# FPGA_Power.net
KiCad netlist of a schematic drawn in Altium Designer
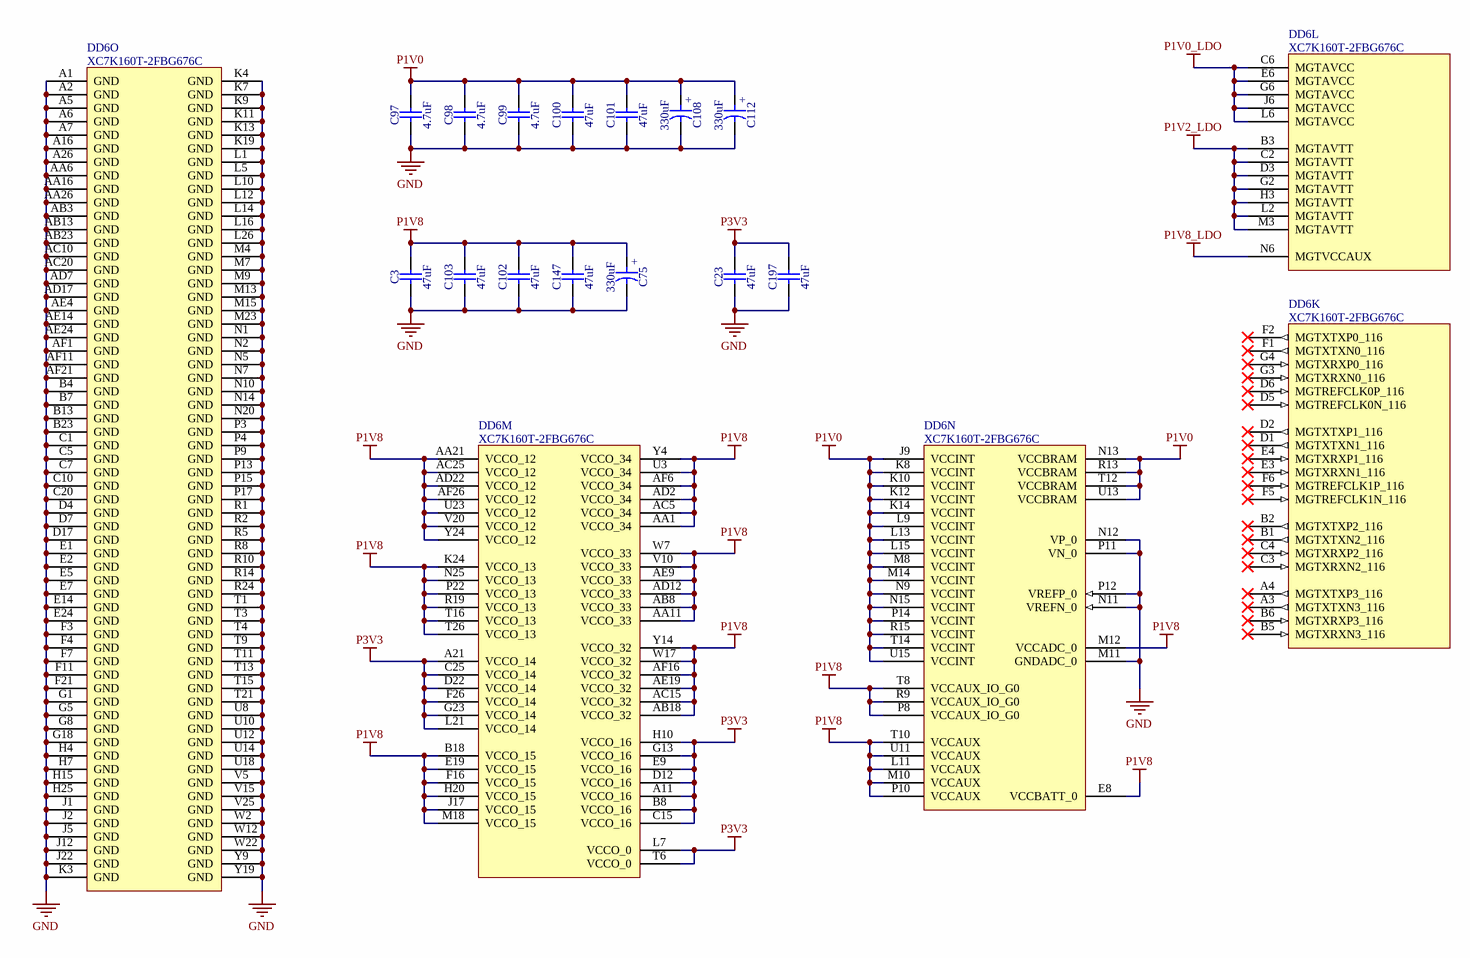
[diagram p0: FPGA_Power.SchDoc]

(export (version "E")
  (design (tool "Eeschema 10.0.6"))
  (components
    (comp (ref "C3")
      (value "47uF")
      (footprint "CAPC3225X270N")
      (description "Non-polarised capacitor")
      (fields
        (field (name "PART NUMBER") "CC1210_47UF_16V_20%_X5R")
        (field (name "VOLTAGE") "16V")
        (field (name "AUTHOR") "CERN DEM MR")
      )
      (libsource (lib "Capacitors") (part "Capacitor - non polarized"))
    )
    (comp (ref "C23")
      (value "47uF")
      (footprint "CAPC3225X270N")
      (description "Non-polarised capacitor")
      (fields
        (field (name "PART NUMBER") "CC1210_47UF_16V_20%_X5R")
        (field (name "VOLTAGE") "16V")
        (field (name "AUTHOR") "CERN DEM MR")
      )
      (libsource (lib "Capacitors") (part "Capacitor - non polarized"))
    )
    (comp (ref "C75")
      (value "330uF")
      (footprint "CAPMP7343X300N")
      (description "Polarised capacitor")
      (fields
        (field (name "PART NUMBER") "CTE7343-30_330UF_4V_20%_PANASONIC_TPF")
        (field (name "VOLTAGE") "4V")
        (field (name "AUTHOR") "CERN DEM HF")
      )
      (libsource (lib "Capacitors") (part "Capacitor - polarized"))
    )
    (comp (ref "C97")
      (value "4.7uF")
      (footprint "CAPC2012X145N")
      (description "Non-polarised capacitor")
      (fields
        (field (name "PART NUMBER") "CC0805_4.7UF_50V_10%_X7R")
        (field (name "VOLTAGE") "50V")
        (field (name "AUTHOR") "CERN DEM JMW")
      )
      (libsource (lib "Capacitors") (part "Capacitor - non polarized"))
    )
    (comp (ref "C98")
      (value "4.7uF")
      (footprint "CAPC2012X145N")
      (description "Non-polarised capacitor")
      (fields
        (field (name "PART NUMBER") "CC0805_4.7UF_50V_10%_X7R")
        (field (name "VOLTAGE") "50V")
        (field (name "AUTHOR") "CERN DEM JMW")
      )
      (libsource (lib "Capacitors") (part "Capacitor - non polarized"))
    )
    (comp (ref "C99")
      (value "4.7uF")
      (footprint "CAPC2012X145N")
      (description "Non-polarised capacitor")
      (fields
        (field (name "PART NUMBER") "CC0805_4.7UF_50V_10%_X7R")
        (field (name "VOLTAGE") "50V")
        (field (name "AUTHOR") "CERN DEM JMW")
      )
      (libsource (lib "Capacitors") (part "Capacitor - non polarized"))
    )
    (comp (ref "C100")
      (value "47uF")
      (footprint "CAPC3225X270N")
      (description "Non-polarised capacitor")
      (fields
        (field (name "PART NUMBER") "CC1210_47UF_16V_20%_X5R")
        (field (name "VOLTAGE") "16V")
        (field (name "AUTHOR") "CERN DEM MR")
      )
      (libsource (lib "Capacitors") (part "Capacitor - non polarized"))
    )
    (comp (ref "C101")
      (value "47uF")
      (footprint "CAPC3225X270N")
      (description "Non-polarised capacitor")
      (fields
        (field (name "PART NUMBER") "CC1210_47UF_16V_20%_X5R")
        (field (name "VOLTAGE") "16V")
        (field (name "AUTHOR") "CERN DEM MR")
      )
      (libsource (lib "Capacitors") (part "Capacitor - non polarized"))
    )
    (comp (ref "C102")
      (value "47uF")
      (footprint "CAPC3225X270N")
      (description "Non-polarised capacitor")
      (fields
        (field (name "PART NUMBER") "CC1210_47UF_16V_20%_X5R")
        (field (name "VOLTAGE") "16V")
        (field (name "AUTHOR") "CERN DEM MR")
      )
      (libsource (lib "Capacitors") (part "Capacitor - non polarized"))
    )
    (comp (ref "C103")
      (value "47uF")
      (footprint "CAPC3225X270N")
      (description "Non-polarised capacitor")
      (fields
        (field (name "PART NUMBER") "CC1210_47UF_16V_20%_X5R")
        (field (name "VOLTAGE") "16V")
        (field (name "AUTHOR") "CERN DEM MR")
      )
      (libsource (lib "Capacitors") (part "Capacitor - non polarized"))
    )
    (comp (ref "C108")
      (value "330uF")
      (footprint "CAPMP7343X190N")
      (description "Polarised capacitor")
      (fields
        (field (name "PART NUMBER") "CTE7343-19_330UF_2.5V_20%_LESR0009_KEMET_T520")
        (field (name "VOLTAGE") "2.5V")
        (field (name "AUTHOR") "CERN DEM HF")
      )
      (libsource (lib "Capacitors") (part "Capacitor - polarized"))
    )
    (comp (ref "C112")
      (value "330uF")
      (footprint "CAPMP7343X190N")
      (description "Polarised capacitor")
      (fields
        (field (name "PART NUMBER") "CTE7343-19_330UF_2.5V_20%_LESR0009_KEMET_T520")
        (field (name "VOLTAGE") "2.5V")
        (field (name "AUTHOR") "CERN DEM HF")
      )
      (libsource (lib "Capacitors") (part "Capacitor - polarized"))
    )
    (comp (ref "C147")
      (value "47uF")
      (footprint "CAPC3225X270N")
      (description "Non-polarised capacitor")
      (fields
        (field (name "PART NUMBER") "CC1210_47UF_16V_20%_X5R")
        (field (name "VOLTAGE") "16V")
        (field (name "AUTHOR") "CERN DEM MR")
      )
      (libsource (lib "Capacitors") (part "Capacitor - non polarized"))
    )
    (comp (ref "C197")
      (value "47uF")
      (footprint "CAPC3225X270N")
      (description "Non-polarised capacitor")
      (fields
        (field (name "PART NUMBER") "CC1210_47UF_16V_20%_X5R")
        (field (name "VOLTAGE") "16V")
        (field (name "AUTHOR") "CERN DEM MR")
      )
      (libsource (lib "Capacitors") (part "Capacitor - non polarized"))
    )
    (comp (ref "DD6")
      (value "XC7K160T-2FBG676C")
      (footprint "BGA676C100P26X26_2700X2700X254")
      (description "KINTEX-7, FPGA, 676-Ball BGA, Pb-Free")
      (fields (field (name "MANUFACTURER") "XILINX") (field (name "AUTHOR") "CERN DEM BC"))
      (libsource (lib "ICs And Semiconductors") (part "XC7K160T-xFBG676"))
    )
  )
  (nets
    (net (code "1") (name "GND") (class "Default")
      (node (ref "C100") (pin "1") (pinfunction "1_1") (pintype "passive"))
      (node (ref "C101") (pin "1") (pinfunction "1_1") (pintype "passive"))
      (node (ref "C102") (pin "1") (pinfunction "1_1") (pintype "passive"))
      (node (ref "C103") (pin "1") (pinfunction "1_1") (pintype "passive"))
      (node (ref "C108") (pin "2") (pinfunction "2_2") (pintype "passive"))
      (node (ref "C112") (pin "2") (pinfunction "2_2") (pintype "passive"))
      (node (ref "C147") (pin "1") (pinfunction "1_1") (pintype "passive"))
      (node (ref "C197") (pin "1") (pinfunction "1_1") (pintype "passive"))
      (node (ref "C23") (pin "1") (pinfunction "1_1") (pintype "passive"))
      (node (ref "C3") (pin "1") (pinfunction "1_1") (pintype "passive"))
      (node (ref "C75") (pin "2") (pinfunction "2_2") (pintype "passive"))
      (node (ref "C97") (pin "1") (pinfunction "1_1") (pintype "passive"))
      (node (ref "C98") (pin "1") (pinfunction "1_1") (pintype "passive"))
      (node (ref "C99") (pin "1") (pinfunction "1_1") (pintype "passive"))
      (node (ref "DD6") (pin "A1") (pinfunction "GND_A1") (pintype "power_in"))
      (node (ref "DD6") (pin "A16") (pinfunction "GND_A16") (pintype "power_in"))
      (node (ref "DD6") (pin "A2") (pinfunction "GND_A2") (pintype "power_in"))
      (node (ref "DD6") (pin "A26") (pinfunction "GND_A26") (pintype "power_in"))
      (node (ref "DD6") (pin "A5") (pinfunction "GND_A5") (pintype "power_in"))
      (node (ref "DD6") (pin "A6") (pinfunction "GND_A6") (pintype "power_in"))
      (node (ref "DD6") (pin "A7") (pinfunction "GND_A7") (pintype "power_in"))
      (node (ref "DD6") (pin "AA16") (pinfunction "GND_AA16") (pintype "power_in"))
      (node (ref "DD6") (pin "AA26") (pinfunction "GND_AA26") (pintype "power_in"))
      (node (ref "DD6") (pin "AA6") (pinfunction "GND_AA6") (pintype "power_in"))
      (node (ref "DD6") (pin "AB13") (pinfunction "GND_AB13") (pintype "power_in"))
      (node (ref "DD6") (pin "AB23") (pinfunction "GND_AB23") (pintype "power_in"))
      (node (ref "DD6") (pin "AB3") (pinfunction "GND_AB3") (pintype "power_in"))
      (node (ref "DD6") (pin "AC10") (pinfunction "GND_AC10") (pintype "power_in"))
      (node (ref "DD6") (pin "AC20") (pinfunction "GND_AC20") (pintype "power_in"))
      (node (ref "DD6") (pin "AD17") (pinfunction "GND_AD17") (pintype "power_in"))
      (node (ref "DD6") (pin "AD7") (pinfunction "GND_AD7") (pintype "power_in"))
      (node (ref "DD6") (pin "AE14") (pinfunction "GND_AE14") (pintype "power_in"))
      (node (ref "DD6") (pin "AE24") (pinfunction "GND_AE24") (pintype "power_in"))
      (node (ref "DD6") (pin "AE4") (pinfunction "GND_AE4") (pintype "power_in"))
      (node (ref "DD6") (pin "AF1") (pinfunction "GND_AF1") (pintype "power_in"))
      (node (ref "DD6") (pin "AF11") (pinfunction "GND_AF11") (pintype "power_in"))
      (node (ref "DD6") (pin "AF21") (pinfunction "GND_AF21") (pintype "power_in"))
      (node (ref "DD6") (pin "B13") (pinfunction "GND_B13") (pintype "power_in"))
      (node (ref "DD6") (pin "B23") (pinfunction "GND_B23") (pintype "power_in"))
      (node (ref "DD6") (pin "B4") (pinfunction "GND_B4") (pintype "power_in"))
      (node (ref "DD6") (pin "B7") (pinfunction "GND_B7") (pintype "power_in"))
      (node (ref "DD6") (pin "C1") (pinfunction "GND_C1") (pintype "power_in"))
      (node (ref "DD6") (pin "C10") (pinfunction "GND_C10") (pintype "power_in"))
      (node (ref "DD6") (pin "C20") (pinfunction "GND_C20") (pintype "power_in"))
      (node (ref "DD6") (pin "C5") (pinfunction "GND_C5") (pintype "power_in"))
      (node (ref "DD6") (pin "C7") (pinfunction "GND_C7") (pintype "power_in"))
      (node (ref "DD6") (pin "D17") (pinfunction "GND_D17") (pintype "power_in"))
      (node (ref "DD6") (pin "D4") (pinfunction "GND_D4") (pintype "power_in"))
      (node (ref "DD6") (pin "D7") (pinfunction "GND_D7") (pintype "power_in"))
      (node (ref "DD6") (pin "E1") (pinfunction "GND_E1") (pintype "power_in"))
      (node (ref "DD6") (pin "E14") (pinfunction "GND_E14") (pintype "power_in"))
      (node (ref "DD6") (pin "E2") (pinfunction "GND_E2") (pintype "power_in"))
      (node (ref "DD6") (pin "E24") (pinfunction "GND_E24") (pintype "power_in"))
      (node (ref "DD6") (pin "E5") (pinfunction "GND_E5") (pintype "power_in"))
      (node (ref "DD6") (pin "E7") (pinfunction "GND_E7") (pintype "power_in"))
      (node (ref "DD6") (pin "F11") (pinfunction "GND_F11") (pintype "power_in"))
      (node (ref "DD6") (pin "F21") (pinfunction "GND_F21") (pintype "power_in"))
      (node (ref "DD6") (pin "F3") (pinfunction "GND_F3") (pintype "power_in"))
      (node (ref "DD6") (pin "F4") (pinfunction "GND_F4") (pintype "power_in"))
      (node (ref "DD6") (pin "F7") (pinfunction "GND_F7") (pintype "power_in"))
      (node (ref "DD6") (pin "G1") (pinfunction "GND_G1") (pintype "power_in"))
      (node (ref "DD6") (pin "G18") (pinfunction "GND_G18") (pintype "power_in"))
      (node (ref "DD6") (pin "G5") (pinfunction "GND_G5") (pintype "power_in"))
      (node (ref "DD6") (pin "G8") (pinfunction "GND_G8") (pintype "power_in"))
      (node (ref "DD6") (pin "H15") (pinfunction "GND_H15") (pintype "power_in"))
      (node (ref "DD6") (pin "H25") (pinfunction "GND_H25") (pintype "power_in"))
      (node (ref "DD6") (pin "H4") (pinfunction "GND_H4") (pintype "power_in"))
      (node (ref "DD6") (pin "H7") (pinfunction "GND_H7") (pintype "power_in"))
      (node (ref "DD6") (pin "J1") (pinfunction "GND_J1") (pintype "power_in"))
      (node (ref "DD6") (pin "J12") (pinfunction "GND_J12") (pintype "power_in"))
      (node (ref "DD6") (pin "J2") (pinfunction "GND_J2") (pintype "power_in"))
      (node (ref "DD6") (pin "J22") (pinfunction "GND_J22") (pintype "power_in"))
      (node (ref "DD6") (pin "J5") (pinfunction "GND_J5") (pintype "power_in"))
      (node (ref "DD6") (pin "K11") (pinfunction "GND_K11") (pintype "power_in"))
      (node (ref "DD6") (pin "K13") (pinfunction "GND_K13") (pintype "power_in"))
      (node (ref "DD6") (pin "K19") (pinfunction "GND_K19") (pintype "power_in"))
      (node (ref "DD6") (pin "K3") (pinfunction "GND_K3") (pintype "power_in"))
      (node (ref "DD6") (pin "K4") (pinfunction "GND_K4") (pintype "power_in"))
      (node (ref "DD6") (pin "K7") (pinfunction "GND_K7") (pintype "power_in"))
      (node (ref "DD6") (pin "K9") (pinfunction "GND_K9") (pintype "power_in"))
      (node (ref "DD6") (pin "L1") (pinfunction "GND_L1") (pintype "power_in"))
      (node (ref "DD6") (pin "L10") (pinfunction "GND_L10") (pintype "power_in"))
      (node (ref "DD6") (pin "L12") (pinfunction "GND_L12") (pintype "power_in"))
      (node (ref "DD6") (pin "L14") (pinfunction "GND_L14") (pintype "power_in"))
      (node (ref "DD6") (pin "L16") (pinfunction "GND_L16") (pintype "power_in"))
      (node (ref "DD6") (pin "L26") (pinfunction "GND_L26") (pintype "power_in"))
      (node (ref "DD6") (pin "L5") (pinfunction "GND_L5") (pintype "power_in"))
      (node (ref "DD6") (pin "M11") (pinfunction "GNDADC_0_M11") (pintype "power_in"))
      (node (ref "DD6") (pin "M13") (pinfunction "GND_M13") (pintype "power_in"))
      (node (ref "DD6") (pin "M15") (pinfunction "GND_M15") (pintype "power_in"))
      (node (ref "DD6") (pin "M23") (pinfunction "GND_M23") (pintype "power_in"))
      (node (ref "DD6") (pin "M4") (pinfunction "GND_M4") (pintype "power_in"))
      (node (ref "DD6") (pin "M7") (pinfunction "GND_M7") (pintype "power_in"))
      (node (ref "DD6") (pin "M9") (pinfunction "GND_M9") (pintype "power_in"))
      (node (ref "DD6") (pin "N1") (pinfunction "GND_N1") (pintype "power_in"))
      (node (ref "DD6") (pin "N10") (pinfunction "GND_N10") (pintype "power_in"))
      (node (ref "DD6") (pin "N11") (pinfunction "VREFN_0_N11") (pintype "input"))
      (node (ref "DD6") (pin "N12") (pinfunction "VP_0_N12") (pintype "power_in"))
      (node (ref "DD6") (pin "N14") (pinfunction "GND_N14") (pintype "power_in"))
      (node (ref "DD6") (pin "N2") (pinfunction "GND_N2") (pintype "power_in"))
      (node (ref "DD6") (pin "N20") (pinfunction "GND_N20") (pintype "power_in"))
      (node (ref "DD6") (pin "N5") (pinfunction "GND_N5") (pintype "power_in"))
      (node (ref "DD6") (pin "N7") (pinfunction "GND_N7") (pintype "power_in"))
      (node (ref "DD6") (pin "P11") (pinfunction "VN_0_P11") (pintype "power_in"))
      (node (ref "DD6") (pin "P12") (pinfunction "VREFP_0_P12") (pintype "input"))
      (node (ref "DD6") (pin "P13") (pinfunction "GND_P13") (pintype "power_in"))
      (node (ref "DD6") (pin "P15") (pinfunction "GND_P15") (pintype "power_in"))
      (node (ref "DD6") (pin "P17") (pinfunction "GND_P17") (pintype "power_in"))
      (node (ref "DD6") (pin "P3") (pinfunction "GND_P3") (pintype "power_in"))
      (node (ref "DD6") (pin "P4") (pinfunction "GND_P4") (pintype "power_in"))
      (node (ref "DD6") (pin "P9") (pinfunction "GND_P9") (pintype "power_in"))
      (node (ref "DD6") (pin "R1") (pinfunction "GND_R1") (pintype "power_in"))
      (node (ref "DD6") (pin "R10") (pinfunction "GND_R10") (pintype "power_in"))
      (node (ref "DD6") (pin "R14") (pinfunction "GND_R14") (pintype "power_in"))
      (node (ref "DD6") (pin "R2") (pinfunction "GND_R2") (pintype "power_in"))
      (node (ref "DD6") (pin "R24") (pinfunction "GND_R24") (pintype "power_in"))
      (node (ref "DD6") (pin "R5") (pinfunction "GND_R5") (pintype "power_in"))
      (node (ref "DD6") (pin "R8") (pinfunction "GND_R8") (pintype "power_in"))
      (node (ref "DD6") (pin "T1") (pinfunction "GND_T1") (pintype "power_in"))
      (node (ref "DD6") (pin "T11") (pinfunction "GND_T11") (pintype "power_in"))
      (node (ref "DD6") (pin "T13") (pinfunction "GND_T13") (pintype "power_in"))
      (node (ref "DD6") (pin "T15") (pinfunction "GND_T15") (pintype "power_in"))
      (node (ref "DD6") (pin "T21") (pinfunction "GND_T21") (pintype "power_in"))
      (node (ref "DD6") (pin "T3") (pinfunction "GND_T3") (pintype "power_in"))
      (node (ref "DD6") (pin "T4") (pinfunction "GND_T4") (pintype "power_in"))
      (node (ref "DD6") (pin "T9") (pinfunction "GND_T9") (pintype "power_in"))
      (node (ref "DD6") (pin "U10") (pinfunction "GND_U10") (pintype "power_in"))
      (node (ref "DD6") (pin "U12") (pinfunction "GND_U12") (pintype "power_in"))
      (node (ref "DD6") (pin "U14") (pinfunction "GND_U14") (pintype "power_in"))
      (node (ref "DD6") (pin "U18") (pinfunction "GND_U18") (pintype "power_in"))
      (node (ref "DD6") (pin "U8") (pinfunction "GND_U8") (pintype "power_in"))
      (node (ref "DD6") (pin "V15") (pinfunction "GND_V15") (pintype "power_in"))
      (node (ref "DD6") (pin "V25") (pinfunction "GND_V25") (pintype "power_in"))
      (node (ref "DD6") (pin "V5") (pinfunction "GND_V5") (pintype "power_in"))
      (node (ref "DD6") (pin "W12") (pinfunction "GND_W12") (pintype "power_in"))
      (node (ref "DD6") (pin "W2") (pinfunction "GND_W2") (pintype "power_in"))
      (node (ref "DD6") (pin "W22") (pinfunction "GND_W22") (pintype "power_in"))
      (node (ref "DD6") (pin "Y19") (pinfunction "GND_Y19") (pintype "power_in"))
      (node (ref "DD6") (pin "Y9") (pinfunction "GND_Y9") (pintype "power_in"))
    )
    (net (code "2") (name "P1V0") (class "Default")
      (node (ref "C100") (pin "2") (pinfunction "2_2") (pintype "passive"))
      (node (ref "C101") (pin "2") (pinfunction "2_2") (pintype "passive"))
      (node (ref "C108") (pin "1") (pinfunction "1_1") (pintype "passive"))
      (node (ref "C112") (pin "1") (pinfunction "1_1") (pintype "passive"))
      (node (ref "C97") (pin "2") (pinfunction "2_2") (pintype "passive"))
      (node (ref "C98") (pin "2") (pinfunction "2_2") (pintype "passive"))
      (node (ref "C99") (pin "2") (pinfunction "2_2") (pintype "passive"))
      (node (ref "DD6") (pin "J9") (pinfunction "VCCINT_J9") (pintype "power_in"))
      (node (ref "DD6") (pin "K10") (pinfunction "VCCINT_K10") (pintype "power_in"))
      (node (ref "DD6") (pin "K12") (pinfunction "VCCINT_K12") (pintype "power_in"))
      (node (ref "DD6") (pin "K14") (pinfunction "VCCINT_K14") (pintype "power_in"))
      (node (ref "DD6") (pin "K8") (pinfunction "VCCINT_K8") (pintype "power_in"))
      (node (ref "DD6") (pin "L13") (pinfunction "VCCINT_L13") (pintype "power_in"))
      (node (ref "DD6") (pin "L15") (pinfunction "VCCINT_L15") (pintype "power_in"))
      (node (ref "DD6") (pin "L9") (pinfunction "VCCINT_L9") (pintype "power_in"))
      (node (ref "DD6") (pin "M14") (pinfunction "VCCINT_M14") (pintype "power_in"))
      (node (ref "DD6") (pin "M8") (pinfunction "VCCINT_M8") (pintype "power_in"))
      (node (ref "DD6") (pin "N13") (pinfunction "VCCBRAM_N13") (pintype "power_in"))
      (node (ref "DD6") (pin "N15") (pinfunction "VCCINT_N15") (pintype "power_in"))
      (node (ref "DD6") (pin "N9") (pinfunction "VCCINT_N9") (pintype "power_in"))
      (node (ref "DD6") (pin "P14") (pinfunction "VCCINT_P14") (pintype "power_in"))
      (node (ref "DD6") (pin "R13") (pinfunction "VCCBRAM_R13") (pintype "power_in"))
      (node (ref "DD6") (pin "R15") (pinfunction "VCCINT_R15") (pintype "power_in"))
      (node (ref "DD6") (pin "T12") (pinfunction "VCCBRAM_T12") (pintype "power_in"))
      (node (ref "DD6") (pin "T14") (pinfunction "VCCINT_T14") (pintype "power_in"))
      (node (ref "DD6") (pin "U13") (pinfunction "VCCBRAM_U13") (pintype "power_in"))
      (node (ref "DD6") (pin "U15") (pinfunction "VCCINT_U15") (pintype "power_in"))
    )
    (net (code "3") (name "P1V0_LDO") (class "Default")
      (node (ref "DD6") (pin "C6") (pinfunction "MGTAVCC_C6") (pintype "power_in"))
      (node (ref "DD6") (pin "E6") (pinfunction "MGTAVCC_E6") (pintype "power_in"))
      (node (ref "DD6") (pin "G6") (pinfunction "MGTAVCC_G6") (pintype "power_in"))
      (node (ref "DD6") (pin "J6") (pinfunction "MGTAVCC_J6") (pintype "power_in"))
      (node (ref "DD6") (pin "L6") (pinfunction "MGTAVCC_L6") (pintype "power_in"))
    )
    (net (code "4") (name "P1V2_LDO") (class "Default")
      (node (ref "DD6") (pin "B3") (pinfunction "MGTAVTT_B3") (pintype "power_in"))
      (node (ref "DD6") (pin "C2") (pinfunction "MGTAVTT_C2") (pintype "power_in"))
      (node (ref "DD6") (pin "D3") (pinfunction "MGTAVTT_D3") (pintype "power_in"))
      (node (ref "DD6") (pin "G2") (pinfunction "MGTAVTT_G2") (pintype "power_in"))
      (node (ref "DD6") (pin "H3") (pinfunction "MGTAVTT_H3") (pintype "power_in"))
      (node (ref "DD6") (pin "L2") (pinfunction "MGTAVTT_L2") (pintype "power_in"))
      (node (ref "DD6") (pin "M3") (pinfunction "MGTAVTT_M3") (pintype "power_in"))
    )
    (net (code "5") (name "P1V8") (class "Default")
      (node (ref "C102") (pin "2") (pinfunction "2_2") (pintype "passive"))
      (node (ref "C103") (pin "2") (pinfunction "2_2") (pintype "passive"))
      (node (ref "C147") (pin "2") (pinfunction "2_2") (pintype "passive"))
      (node (ref "C3") (pin "2") (pinfunction "2_2") (pintype "passive"))
      (node (ref "C75") (pin "1") (pinfunction "1_1") (pintype "passive"))
      (node (ref "DD6") (pin "AA1") (pinfunction "VCCO_34_AA1") (pintype "power_in"))
      (node (ref "DD6") (pin "AA11") (pinfunction "VCCO_33_AA11") (pintype "power_in"))
      (node (ref "DD6") (pin "AA21") (pinfunction "VCCO_12_AA21") (pintype "power_in"))
      (node (ref "DD6") (pin "AB18") (pinfunction "VCCO_32_AB18") (pintype "power_in"))
      (node (ref "DD6") (pin "AB8") (pinfunction "VCCO_33_AB8") (pintype "power_in"))
      (node (ref "DD6") (pin "AC15") (pinfunction "VCCO_32_AC15") (pintype "power_in"))
      (node (ref "DD6") (pin "AC25") (pinfunction "VCCO_12_AC25") (pintype "power_in"))
      (node (ref "DD6") (pin "AC5") (pinfunction "VCCO_34_AC5") (pintype "power_in"))
      (node (ref "DD6") (pin "AD12") (pinfunction "VCCO_33_AD12") (pintype "power_in"))
      (node (ref "DD6") (pin "AD2") (pinfunction "VCCO_34_AD2") (pintype "power_in"))
      (node (ref "DD6") (pin "AD22") (pinfunction "VCCO_12_AD22") (pintype "power_in"))
      (node (ref "DD6") (pin "AE19") (pinfunction "VCCO_32_AE19") (pintype "power_in"))
      (node (ref "DD6") (pin "AE9") (pinfunction "VCCO_33_AE9") (pintype "power_in"))
      (node (ref "DD6") (pin "AF16") (pinfunction "VCCO_32_AF16") (pintype "power_in"))
      (node (ref "DD6") (pin "AF26") (pinfunction "VCCO_12_AF26") (pintype "power_in"))
      (node (ref "DD6") (pin "AF6") (pinfunction "VCCO_34_AF6") (pintype "power_in"))
      (node (ref "DD6") (pin "B18") (pinfunction "VCCO_15_B18") (pintype "power_in"))
      (node (ref "DD6") (pin "E19") (pinfunction "VCCO_15_E19") (pintype "power_in"))
      (node (ref "DD6") (pin "E8") (pinfunction "VCCBATT_0_E8") (pintype "power_in"))
      (node (ref "DD6") (pin "F16") (pinfunction "VCCO_15_F16") (pintype "power_in"))
      (node (ref "DD6") (pin "H20") (pinfunction "VCCO_15_H20") (pintype "power_in"))
      (node (ref "DD6") (pin "J17") (pinfunction "VCCO_15_J17") (pintype "power_in"))
      (node (ref "DD6") (pin "K24") (pinfunction "VCCO_13_K24") (pintype "power_in"))
      (node (ref "DD6") (pin "L11") (pinfunction "VCCAUX_L11") (pintype "power_in"))
      (node (ref "DD6") (pin "M10") (pinfunction "VCCAUX_M10") (pintype "power_in"))
      (node (ref "DD6") (pin "M12") (pinfunction "VCCADC_0_M12") (pintype "power_in"))
      (node (ref "DD6") (pin "M18") (pinfunction "VCCO_15_M18") (pintype "power_in"))
      (node (ref "DD6") (pin "N25") (pinfunction "VCCO_13_N25") (pintype "power_in"))
      (node (ref "DD6") (pin "P10") (pinfunction "VCCAUX_P10") (pintype "power_in"))
      (node (ref "DD6") (pin "P22") (pinfunction "VCCO_13_P22") (pintype "power_in"))
      (node (ref "DD6") (pin "P8") (pinfunction "VCCAUX_IO_G0_P8") (pintype "power_in"))
      (node (ref "DD6") (pin "R19") (pinfunction "VCCO_13_R19") (pintype "power_in"))
      (node (ref "DD6") (pin "R9") (pinfunction "VCCAUX_IO_G0_R9") (pintype "power_in"))
      (node (ref "DD6") (pin "T10") (pinfunction "VCCAUX_T10") (pintype "power_in"))
      (node (ref "DD6") (pin "T16") (pinfunction "VCCO_13_T16") (pintype "power_in"))
      (node (ref "DD6") (pin "T26") (pinfunction "VCCO_13_T26") (pintype "power_in"))
      (node (ref "DD6") (pin "T8") (pinfunction "VCCAUX_IO_G0_T8") (pintype "power_in"))
      (node (ref "DD6") (pin "U11") (pinfunction "VCCAUX_U11") (pintype "power_in"))
      (node (ref "DD6") (pin "U23") (pinfunction "VCCO_12_U23") (pintype "power_in"))
      (node (ref "DD6") (pin "U3") (pinfunction "VCCO_34_U3") (pintype "power_in"))
      (node (ref "DD6") (pin "V10") (pinfunction "VCCO_33_V10") (pintype "power_in"))
      (node (ref "DD6") (pin "V20") (pinfunction "VCCO_12_V20") (pintype "power_in"))
      (node (ref "DD6") (pin "W17") (pinfunction "VCCO_32_W17") (pintype "power_in"))
      (node (ref "DD6") (pin "W7") (pinfunction "VCCO_33_W7") (pintype "power_in"))
      (node (ref "DD6") (pin "Y14") (pinfunction "VCCO_32_Y14") (pintype "power_in"))
      (node (ref "DD6") (pin "Y24") (pinfunction "VCCO_12_Y24") (pintype "power_in"))
      (node (ref "DD6") (pin "Y4") (pinfunction "VCCO_34_Y4") (pintype "power_in"))
    )
    (net (code "6") (name "P1V8_LDO") (class "Default")
      (node (ref "DD6") (pin "N6") (pinfunction "MGTVCCAUX_N6") (pintype "power_in"))
    )
    (net (code "7") (name "P3V3") (class "Default")
      (node (ref "C197") (pin "2") (pinfunction "2_2") (pintype "passive"))
      (node (ref "C23") (pin "2") (pinfunction "2_2") (pintype "passive"))
      (node (ref "DD6") (pin "A11") (pinfunction "VCCO_16_A11") (pintype "power_in"))
      (node (ref "DD6") (pin "A21") (pinfunction "VCCO_14_A21") (pintype "power_in"))
      (node (ref "DD6") (pin "B8") (pinfunction "VCCO_16_B8") (pintype "power_in"))
      (node (ref "DD6") (pin "C15") (pinfunction "VCCO_16_C15") (pintype "power_in"))
      (node (ref "DD6") (pin "C25") (pinfunction "VCCO_14_C25") (pintype "power_in"))
      (node (ref "DD6") (pin "D12") (pinfunction "VCCO_16_D12") (pintype "power_in"))
      (node (ref "DD6") (pin "D22") (pinfunction "VCCO_14_D22") (pintype "power_in"))
      (node (ref "DD6") (pin "E9") (pinfunction "VCCO_16_E9") (pintype "power_in"))
      (node (ref "DD6") (pin "F26") (pinfunction "VCCO_14_F26") (pintype "power_in"))
      (node (ref "DD6") (pin "G13") (pinfunction "VCCO_16_G13") (pintype "power_in"))
      (node (ref "DD6") (pin "G23") (pinfunction "VCCO_14_G23") (pintype "power_in"))
      (node (ref "DD6") (pin "H10") (pinfunction "VCCO_16_H10") (pintype "power_in"))
      (node (ref "DD6") (pin "L21") (pinfunction "VCCO_14_L21") (pintype "power_in"))
      (node (ref "DD6") (pin "L7") (pinfunction "VCCO_0_L7") (pintype "power_in"))
      (node (ref "DD6") (pin "T6") (pinfunction "VCCO_0_T6") (pintype "power_in"))
    )
    (net (code "8") (name "unconnected-(DD6K-MGTREFCLK0N_116-PadD5)") (class "Default")
      (node (ref "DD6") (pin "D5") (pinfunction "MGTREFCLK0N_116_D5") (pintype "input+no_connect"))
    )
    (net (code "9") (name "unconnected-(DD6K-MGTREFCLK0P_116-PadD6)") (class "Default")
      (node (ref "DD6") (pin "D6") (pinfunction "MGTREFCLK0P_116_D6") (pintype "input+no_connect"))
    )
    (net (code "10") (name "unconnected-(DD6K-MGTREFCLK1N_116-PadF5)") (class "Default")
      (node (ref "DD6") (pin "F5") (pinfunction "MGTREFCLK1N_116_F5") (pintype "input+no_connect"))
    )
    (net (code "11") (name "unconnected-(DD6K-MGTREFCLK1P_116-PadF6)") (class "Default")
      (node (ref "DD6") (pin "F6") (pinfunction "MGTREFCLK1P_116_F6") (pintype "input+no_connect"))
    )
    (net (code "12") (name "unconnected-(DD6K-MGTXRXN0_116-PadG3)") (class "Default")
      (node (ref "DD6") (pin "G3") (pinfunction "MGTXRXN0_116_G3") (pintype "input+no_connect"))
    )
    (net (code "13") (name "unconnected-(DD6K-MGTXRXN1_116-PadE3)") (class "Default")
      (node (ref "DD6") (pin "E3") (pinfunction "MGTXRXN1_116_E3") (pintype "input+no_connect"))
    )
    (net (code "14") (name "unconnected-(DD6K-MGTXRXN2_116-PadC3)") (class "Default")
      (node (ref "DD6") (pin "C3") (pinfunction "MGTXRXN2_116_C3") (pintype "input+no_connect"))
    )
    (net (code "15") (name "unconnected-(DD6K-MGTXRXN3_116-PadB5)") (class "Default")
      (node (ref "DD6") (pin "B5") (pinfunction "MGTXRXN3_116_B5") (pintype "input+no_connect"))
    )
    (net (code "16") (name "unconnected-(DD6K-MGTXRXP0_116-PadG4)") (class "Default")
      (node (ref "DD6") (pin "G4") (pinfunction "MGTXRXP0_116_G4") (pintype "input+no_connect"))
    )
    (net (code "17") (name "unconnected-(DD6K-MGTXRXP1_116-PadE4)") (class "Default")
      (node (ref "DD6") (pin "E4") (pinfunction "MGTXRXP1_116_E4") (pintype "input+no_connect"))
    )
    (net (code "18") (name "unconnected-(DD6K-MGTXRXP2_116-PadC4)") (class "Default")
      (node (ref "DD6") (pin "C4") (pinfunction "MGTXRXP2_116_C4") (pintype "input+no_connect"))
    )
    (net (code "19") (name "unconnected-(DD6K-MGTXRXP3_116-PadB6)") (class "Default")
      (node (ref "DD6") (pin "B6") (pinfunction "MGTXRXP3_116_B6") (pintype "input+no_connect"))
    )
    (net (code "20") (name "unconnected-(DD6K-MGTXTXN0_116-PadF1)") (class "Default")
      (node (ref "DD6") (pin "F1") (pinfunction "MGTXTXN0_116_F1") (pintype "output+no_connect"))
    )
    (net (code "21") (name "unconnected-(DD6K-MGTXTXN1_116-PadD1)") (class "Default")
      (node (ref "DD6") (pin "D1") (pinfunction "MGTXTXN1_116_D1") (pintype "output+no_connect"))
    )
    (net (code "22") (name "unconnected-(DD6K-MGTXTXN2_116-PadB1)") (class "Default")
      (node (ref "DD6") (pin "B1") (pinfunction "MGTXTXN2_116_B1") (pintype "output+no_connect"))
    )
    (net (code "23") (name "unconnected-(DD6K-MGTXTXN3_116-PadA3)") (class "Default")
      (node (ref "DD6") (pin "A3") (pinfunction "MGTXTXN3_116_A3") (pintype "output+no_connect"))
    )
    (net (code "24") (name "unconnected-(DD6K-MGTXTXP0_116-PadF2)") (class "Default")
      (node (ref "DD6") (pin "F2") (pinfunction "MGTXTXP0_116_F2") (pintype "output+no_connect"))
    )
    (net (code "25") (name "unconnected-(DD6K-MGTXTXP1_116-PadD2)") (class "Default")
      (node (ref "DD6") (pin "D2") (pinfunction "MGTXTXP1_116_D2") (pintype "output+no_connect"))
    )
    (net (code "26") (name "unconnected-(DD6K-MGTXTXP2_116-PadB2)") (class "Default")
      (node (ref "DD6") (pin "B2") (pinfunction "MGTXTXP2_116_B2") (pintype "output+no_connect"))
    )
    (net (code "27") (name "unconnected-(DD6K-MGTXTXP3_116-PadA4)") (class "Default")
      (node (ref "DD6") (pin "A4") (pinfunction "MGTXTXP3_116_A4") (pintype "output+no_connect"))
    )
  )
)
